# Micro-Interactions.net
KiCad netlist of a schematic drawn in EAGLE
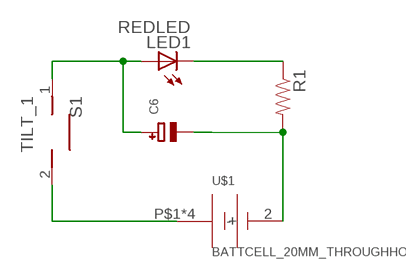
[diagram p0: schematic, sheet 1]

(export (version "E")
  (design (tool "Eeschema 10.0.6"))
  (components
    (comp (ref "C6")
      (value "CAP_ELECTROLYTICPTH_3.5MMGRID_8MMDIA")
      (footprint "eagle-import:CELEC_3.5MM_8MM")
      (libsource (lib "eagle-import") (part "CAP_ELECTROLYTICPTH_3.5MMGRID_8MMDIA"))
    )
    (comp (ref "LED1")
      (value "REDLED")
      (footprint "eagle-import:LED5MM")
      (libsource (lib "eagle-import") (part "LED5MM"))
    )
    (comp (ref "R1")
      (value "RESISTORAXIAL-0.3")
      (footprint "eagle-import:AXIAL-0.3")
      (libsource (lib "eagle-import") (part "RESISTORAXIAL-0.3"))
    )
    (comp (ref "S1")
      (value "TILT_1")
      (footprint "eagle-import:DS-01")
      (libsource (lib "eagle-import") (part "DS01"))
    )
    (comp (ref "U$1")
      (value "BATTCELL_20MM_THROUGHHOLE")
      (footprint "eagle-import:BATTCON_20MM_4LEGS")
      (libsource (lib "eagle-import") (part "BATTCELL_20MM_THROUGHHOLE"))
    )
  )
  (nets
    (net (code "1") (name "Net-(C6-Pad+)") (class "Default")
      (node (ref "C6") (pin "+") (pinfunction "+_+") (pintype "passive"))
      (node (ref "LED1") (pin "A") (pinfunction "A_A") (pintype "passive"))
      (node (ref "S1") (pin "1") (pinfunction "1_1") (pintype "passive"))
    )
    (net (code "2") (name "Net-(LED1-C)") (class "Default")
      (node (ref "LED1") (pin "K") (pinfunction "C_K") (pintype "passive"))
      (node (ref "R1") (pin "P$1") (pinfunction "1_P$1") (pintype "passive"))
    )
    (net (code "3") (name "Net-(R1-2)") (class "Default")
      (node (ref "C6") (pin "-") (pinfunction "-_-") (pintype "passive"))
      (node (ref "R1") (pin "P$2") (pinfunction "2_P$2") (pintype "passive"))
      (node (ref "U$1") (pin "2") (pinfunction "-_2") (pintype "bidirectional"))
    )
    (net (code "4") (name "Net-(S1-Pad2)") (class "Default")
      (node (ref "S1") (pin "2") (pinfunction "2_2") (pintype "passive"))
      (node (ref "U$1") (pin "P$1") (pinfunction "+_P$1") (pintype "bidirectional"))
      (node (ref "U$1") (pin "P$2") (pinfunction "+_P$2") (pintype "bidirectional"))
      (node (ref "U$1") (pin "P$3") (pinfunction "+_P$3") (pintype "bidirectional"))
      (node (ref "U$1") (pin "P$4") (pinfunction "+_P$4") (pintype "bidirectional"))
    )
  )
)
